# lab1_larionov_usb_rs232.net
KiCad netlist of a schematic drawn in Altium Designer
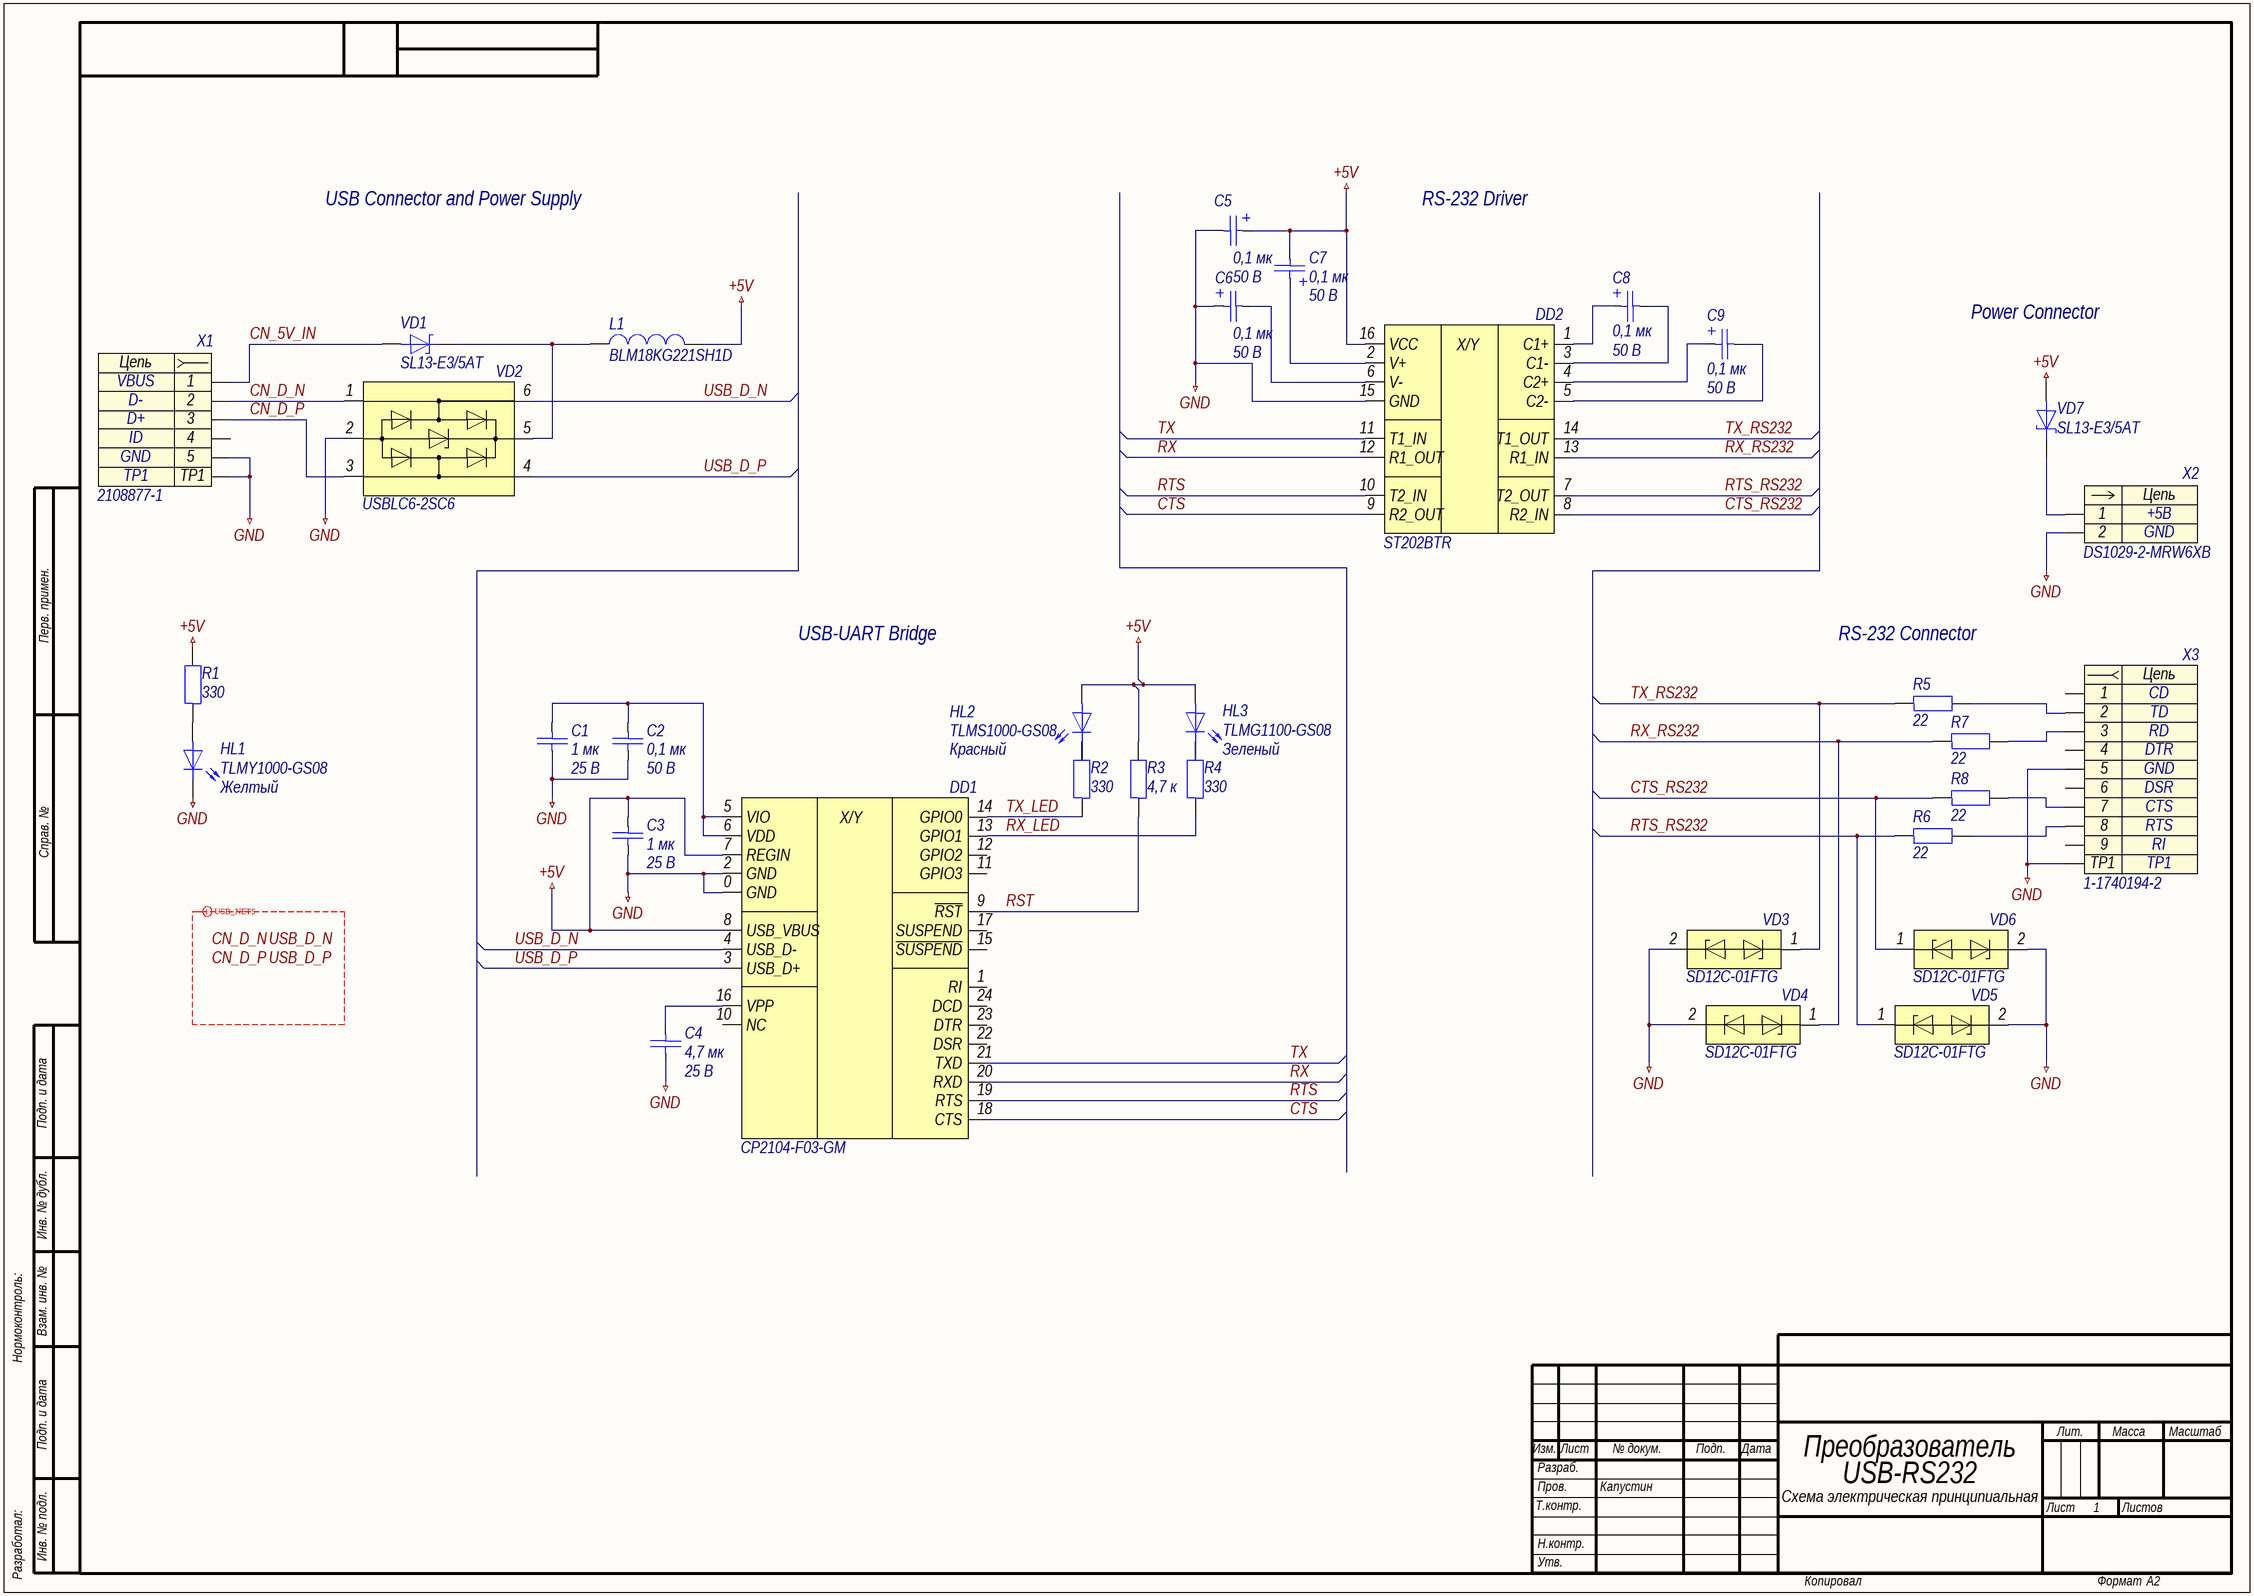
[diagram p0: lab1_larionov_usb_rs232.SchDoc]

(export (version "E")
  (design (tool "Eeschema 10.0.6"))
  (components
    (comp (ref "C1")
      (value "1 мк")
      (footprint "C0603")
      (description "=Описание")
      (fields (field (name "НАПРЯЖЕНИЕ") "25 В"))
      (libsource (lib "Database_Students") (part "CAPACITOR-NONPOLAR"))
    )
    (comp (ref "C2")
      (value "0,1 мк")
      (footprint "C0603")
      (description "=Описание")
      (fields (field (name "НАПРЯЖЕНИЕ") "50 В"))
      (libsource (lib "Database_Students") (part "CAPACITOR-NONPOLAR"))
    )
    (comp (ref "C3")
      (value "1 мк")
      (footprint "C0603")
      (description "=Описание")
      (fields (field (name "НАПРЯЖЕНИЕ") "25 В"))
      (libsource (lib "Database_Students") (part "CAPACITOR-NONPOLAR"))
    )
    (comp (ref "C4")
      (value "4,7 мк")
      (footprint "C0603")
      (description "=Описание")
      (fields (field (name "НАПРЯЖЕНИЕ") "25 В"))
      (libsource (lib "Database_Students") (part "CAPACITOR-NONPOLAR"))
    )
    (comp (ref "C5")
      (value "0,1 мк")
      (footprint "C1206POLAR")
      (description "=Описание")
      (fields (field (name "НАПРЯЖЕНИЕ") "50 В"))
      (libsource (lib "Database_Students") (part "CAPACITOR-POLAR"))
    )
    (comp (ref "C6")
      (value "0,1 мк")
      (footprint "C1206POLAR")
      (description "=Описание")
      (fields (field (name "НАПРЯЖЕНИЕ") "50 В"))
      (libsource (lib "Database_Students") (part "CAPACITOR-POLAR"))
    )
    (comp (ref "C7")
      (value "0,1 мк")
      (footprint "C1206POLAR")
      (description "=Описание")
      (fields (field (name "НАПРЯЖЕНИЕ") "50 В"))
      (libsource (lib "Database_Students") (part "CAPACITOR-POLAR"))
    )
    (comp (ref "C8")
      (value "0,1 мк")
      (footprint "C1206POLAR")
      (description "=Описание")
      (fields (field (name "НАПРЯЖЕНИЕ") "50 В"))
      (libsource (lib "Database_Students") (part "CAPACITOR-POLAR"))
    )
    (comp (ref "C9")
      (value "0,1 мк")
      (footprint "C1206POLAR")
      (description "=Описание")
      (fields (field (name "НАПРЯЖЕНИЕ") "50 В"))
      (libsource (lib "Database_Students") (part "CAPACITOR-POLAR"))
    )
    (comp (ref "DD1")
      (value "CP2104-F03-GM")
      (footprint "QFN-24-400X400X80")
      (description "=Описание")
      (libsource (lib "Database_Students") (part "CP2104-F03-GM"))
    )
    (comp (ref "DD2")
      (value "ST202BTR")
      (footprint "TSSOP-16")
      (description "=Описание")
      (libsource (lib "Database_Students") (part "ST202BTR"))
    )
    (comp (ref "HL1")
      (value "TLMY1000-GS08")
      (footprint "HL0603")
      (description "=Описание")
      (fields (field (name "COLOUR") "Желтый"))
      (libsource (lib "Database_Students") (part "LED-COMMON"))
    )
    (comp (ref "HL2")
      (value "TLMS1000-GS08")
      (footprint "HL0603")
      (description "=Описание")
      (fields (field (name "COLOUR") "Красный"))
      (libsource (lib "Database_Students") (part "LED-COMMON"))
    )
    (comp (ref "HL3")
      (value "TLMG1100-GS08")
      (footprint "HL0603")
      (description "=Описание")
      (fields (field (name "COLOUR") "Зеленый"))
      (libsource (lib "Database_Students") (part "LED-COMMON"))
    )
    (comp (ref "L1")
      (value "BLM18KG221SH1D")
      (footprint "BLM-2-0603")
      (description "=Описание")
      (libsource (lib "Database_Students") (part "FERRITE-BEAD"))
    )
    (comp (ref "R1")
      (value "330")
      (footprint "R0603")
      (description "=Описание")
      (libsource (lib "Database_Students") (part "R-COMMON"))
    )
    (comp (ref "R2")
      (value "330")
      (footprint "R0603")
      (description "=Описание")
      (libsource (lib "Database_Students") (part "R-COMMON"))
    )
    (comp (ref "R3")
      (value "4,7 к")
      (footprint "R0603")
      (description "=Описание")
      (libsource (lib "Database_Students") (part "R-COMMON"))
    )
    (comp (ref "R4")
      (value "330")
      (footprint "R0603")
      (description "=Описание")
      (libsource (lib "Database_Students") (part "R-COMMON"))
    )
    (comp (ref "R5")
      (value "22")
      (footprint "R0603")
      (description "=Описание")
      (libsource (lib "Database_Students") (part "R-COMMON"))
    )
    (comp (ref "R6")
      (value "22")
      (footprint "R0603")
      (description "=Описание")
      (libsource (lib "Database_Students") (part "R-COMMON"))
    )
    (comp (ref "R7")
      (value "22")
      (footprint "R0603")
      (description "=Описание")
      (libsource (lib "Database_Students") (part "R-COMMON"))
    )
    (comp (ref "R8")
      (value "22")
      (footprint "R0603")
      (description "=Описание")
      (libsource (lib "Database_Students") (part "R-COMMON"))
    )
    (comp (ref "VD1")
      (value "SL13-E3/5AT")
      (footprint "DO-214AC")
      (description "=Описание")
      (libsource (lib "Database_Students") (part "DIODE-SCHOTTKY"))
    )
    (comp (ref "VD2")
      (value "USBLC6-2SC6")
      (footprint "SOT-23-6")
      (description "=Описание")
      (libsource (lib "Database_Students") (part "USBLC6-2SC6"))
    )
    (comp (ref "VD3")
      (value "SD12C-01FTG")
      (footprint "SOD-323")
      (description "=Описание")
      (libsource (lib "") (part "ZENER-BI-DIRECTIONAL_1"))
    )
    (comp (ref "VD4")
      (value "SD12C-01FTG")
      (footprint "SOD-323")
      (description "=Описание")
      (libsource (lib "") (part "ZENER-BI-DIRECTIONAL_1"))
    )
    (comp (ref "VD5")
      (value "SD12C-01FTG")
      (footprint "SOD-323")
      (description "=Описание")
      (libsource (lib "Database_Students") (part "ZENER-BI-DIRECTIONAL"))
    )
    (comp (ref "VD6")
      (value "SD12C-01FTG")
      (footprint "SOD-323")
      (description "=Описание")
      (libsource (lib "Database_Students") (part "ZENER-BI-DIRECTIONAL"))
    )
    (comp (ref "VD7")
      (value "SL13-E3/5AT")
      (footprint "DO-214AC")
      (description "=Описание")
      (libsource (lib "Database_Students") (part "DIODE-SCHOTTKY"))
    )
    (comp (ref "X1")
      (value "2108877-1")
      (footprint "2108877-1")
      (libsource (lib "Database_Students") (part "HEADER-5-TP1-SCT"))
    )
    (comp (ref "X2")
      (value "DS1029-2-MRW6XB")
      (footprint "DS1029-2-MRW6XB")
      (description "=Описание")
      (libsource (lib "Database_Students") (part "HEADER-2-PLG"))
    )
    (comp (ref "X3")
      (value "1-1740194-2")
      (footprint "1-1740194-2")
      (libsource (lib "Database_Students") (part "HEADER-9-TP1-SCT"))
    )
  )
  (nets
    (net (code "1") (name "+5V") (class "Default")
      (node (ref "C3") (pin "2") (pinfunction "2_2") (pintype "passive"))
      (node (ref "C5") (pin "1") (pinfunction "1_1") (pintype "passive"))
      (node (ref "C7") (pin "2") (pinfunction "2_2") (pintype "passive"))
      (node (ref "DD1") (pin "7") (pinfunction "REGIN_7") (pintype "passive"))
      (node (ref "DD1") (pin "8") (pinfunction "USB_VBUS_8") (pintype "passive"))
      (node (ref "DD2") (pin "16") (pinfunction "VCC_16") (pintype "passive"))
      (node (ref "HL2") (pin "2") (pinfunction "2_2") (pintype "passive"))
      (node (ref "HL3") (pin "2") (pinfunction "2_2") (pintype "passive"))
      (node (ref "L1") (pin "2") (pinfunction "2_2") (pintype "passive"))
      (node (ref "R1") (pin "2") (pinfunction "2_2") (pintype "passive"))
      (node (ref "R3") (pin "2") (pinfunction "2_2") (pintype "passive"))
      (node (ref "VD7") (pin "2") (pinfunction "2_2") (pintype "passive"))
    )
    (net (code "2") (name "/CN_5V_IN") (class "Default")
      (node (ref "VD1") (pin "2") (pinfunction "2_2") (pintype "passive"))
      (node (ref "X1") (pin "1") (pinfunction "1_1") (pintype "passive"))
    )
    (net (code "3") (name "/CN_D_N") (class "Default")
      (node (ref "VD2") (pin "1") (pinfunction "1_1") (pintype "passive"))
      (node (ref "X1") (pin "2") (pinfunction "2_2") (pintype "passive"))
    )
    (net (code "4") (name "/CN_D_P") (class "Default")
      (node (ref "VD2") (pin "3") (pinfunction "3_3") (pintype "passive"))
      (node (ref "X1") (pin "3") (pinfunction "3_3") (pintype "passive"))
    )
    (net (code "5") (name "/CTS") (class "Default")
      (node (ref "DD1") (pin "18") (pinfunction "CTS_18") (pintype "passive"))
      (node (ref "DD2") (pin "9") (pinfunction "R2_OUT_9") (pintype "passive"))
    )
    (net (code "6") (name "/CTS_RS232") (class "Default")
      (node (ref "DD2") (pin "8") (pinfunction "R2_IN_8") (pintype "passive"))
      (node (ref "R8") (pin "1") (pinfunction "1_1") (pintype "passive"))
      (node (ref "VD6") (pin "1") (pinfunction "1_1") (pintype "passive"))
    )
    (net (code "7") (name "/RST") (class "Default")
      (node (ref "DD1") (pin "9") (pinfunction "~{RST}_9") (pintype "passive"))
      (node (ref "R3") (pin "1") (pinfunction "1_1") (pintype "passive"))
    )
    (net (code "8") (name "/RTS") (class "Default")
      (node (ref "DD1") (pin "19") (pinfunction "RTS_19") (pintype "passive"))
      (node (ref "DD2") (pin "10") (pinfunction "T2_IN_10") (pintype "passive"))
    )
    (net (code "9") (name "/RTS_RS232") (class "Default")
      (node (ref "DD2") (pin "7") (pinfunction "T2_OUT_7") (pintype "passive"))
      (node (ref "R6") (pin "1") (pinfunction "1_1") (pintype "passive"))
      (node (ref "VD5") (pin "1") (pinfunction "1_1") (pintype "passive"))
    )
    (net (code "10") (name "/RX") (class "Default")
      (node (ref "DD1") (pin "20") (pinfunction "RXD_20") (pintype "passive"))
      (node (ref "DD2") (pin "12") (pinfunction "R1_OUT_12") (pintype "passive"))
    )
    (net (code "11") (name "/RX_LED") (class "Default")
      (node (ref "DD1") (pin "13") (pinfunction "GPIO1_13") (pintype "passive"))
      (node (ref "R4") (pin "1") (pinfunction "1_1") (pintype "passive"))
    )
    (net (code "12") (name "/RX_RS232") (class "Default")
      (node (ref "DD2") (pin "13") (pinfunction "R1_IN_13") (pintype "passive"))
      (node (ref "R7") (pin "1") (pinfunction "1_1") (pintype "passive"))
      (node (ref "VD4") (pin "1") (pinfunction "1_1") (pintype "passive"))
    )
    (net (code "13") (name "/TX") (class "Default")
      (node (ref "DD1") (pin "21") (pinfunction "TXD_21") (pintype "passive"))
      (node (ref "DD2") (pin "11") (pinfunction "T1_IN_11") (pintype "passive"))
    )
    (net (code "14") (name "/TX_LED") (class "Default")
      (node (ref "DD1") (pin "14") (pinfunction "GPIO0_14") (pintype "passive"))
      (node (ref "R2") (pin "1") (pinfunction "1_1") (pintype "passive"))
    )
    (net (code "15") (name "/TX_RS232") (class "Default")
      (node (ref "DD2") (pin "14") (pinfunction "T1_OUT_14") (pintype "passive"))
      (node (ref "R5") (pin "1") (pinfunction "1_1") (pintype "passive"))
      (node (ref "VD3") (pin "1") (pinfunction "1_1") (pintype "passive"))
    )
    (net (code "16") (name "/USB_D_N") (class "Default")
      (node (ref "DD1") (pin "4") (pinfunction "USB_D-_4") (pintype "passive"))
      (node (ref "VD2") (pin "6") (pinfunction "6_6") (pintype "passive"))
    )
    (net (code "17") (name "/USB_D_P") (class "Default")
      (node (ref "DD1") (pin "3") (pinfunction "USB_D+_3") (pintype "passive"))
      (node (ref "VD2") (pin "4") (pinfunction "4_4") (pintype "passive"))
    )
    (net (code "18") (name "GND") (class "Default")
      (node (ref "C1") (pin "1") (pinfunction "1_1") (pintype "passive"))
      (node (ref "C2") (pin "1") (pinfunction "1_1") (pintype "passive"))
      (node (ref "C3") (pin "1") (pinfunction "1_1") (pintype "passive"))
      (node (ref "C4") (pin "1") (pinfunction "1_1") (pintype "passive"))
      (node (ref "C5") (pin "2") (pinfunction "2_2") (pintype "passive"))
      (node (ref "C6") (pin "1") (pinfunction "1_1") (pintype "passive"))
      (node (ref "DD1") (pin "0") (pinfunction "GND_0") (pintype "passive"))
      (node (ref "DD1") (pin "2") (pinfunction "GND_2") (pintype "passive"))
      (node (ref "DD2") (pin "15") (pinfunction "GND_15") (pintype "passive"))
      (node (ref "HL1") (pin "1") (pinfunction "1_1") (pintype "passive"))
      (node (ref "VD2") (pin "2") (pinfunction "2_2") (pintype "passive"))
      (node (ref "VD3") (pin "2") (pinfunction "2_2") (pintype "passive"))
      (node (ref "VD4") (pin "2") (pinfunction "2_2") (pintype "passive"))
      (node (ref "VD5") (pin "2") (pinfunction "2_2") (pintype "passive"))
      (node (ref "VD6") (pin "2") (pinfunction "2_2") (pintype "passive"))
      (node (ref "X1") (pin "5") (pinfunction "5_5") (pintype "passive"))
      (node (ref "X1") (pin "TP1") (pinfunction "TP1_TP1") (pintype "passive"))
      (node (ref "X2") (pin "2") (pinfunction "2_2") (pintype "passive"))
      (node (ref "X3") (pin "5") (pinfunction "5_5") (pintype "passive"))
      (node (ref "X3") (pin "TP1") (pinfunction "TP1_TP1") (pintype "passive"))
    )
    (net (code "19") (name "Net-(DD1-VDD)") (class "Default")
      (node (ref "C1") (pin "2") (pinfunction "2_2") (pintype "passive"))
      (node (ref "C2") (pin "2") (pinfunction "2_2") (pintype "passive"))
      (node (ref "DD1") (pin "5") (pinfunction "VIO_5") (pintype "passive"))
      (node (ref "DD1") (pin "6") (pinfunction "VDD_6") (pintype "passive"))
    )
    (net (code "20") (name "Net-(DD1-VPP)") (class "Default")
      (node (ref "C4") (pin "2") (pinfunction "2_2") (pintype "passive"))
      (node (ref "DD1") (pin "16") (pinfunction "VPP_16") (pintype "passive"))
    )
    (net (code "21") (name "Net-(DD2-C1+)") (class "Default")
      (node (ref "C8") (pin "1") (pinfunction "1_1") (pintype "passive"))
      (node (ref "DD2") (pin "1") (pinfunction "C1+_1") (pintype "passive"))
    )
    (net (code "22") (name "Net-(DD2-C1-)") (class "Default")
      (node (ref "C8") (pin "2") (pinfunction "2_2") (pintype "passive"))
      (node (ref "DD2") (pin "3") (pinfunction "C1-_3") (pintype "passive"))
    )
    (net (code "23") (name "Net-(DD2-C2+)") (class "Default")
      (node (ref "C9") (pin "1") (pinfunction "1_1") (pintype "passive"))
      (node (ref "DD2") (pin "4") (pinfunction "C2+_4") (pintype "passive"))
    )
    (net (code "24") (name "Net-(DD2-C2-)") (class "Default")
      (node (ref "C9") (pin "2") (pinfunction "2_2") (pintype "passive"))
      (node (ref "DD2") (pin "5") (pinfunction "C2-_5") (pintype "passive"))
    )
    (net (code "25") (name "Net-(DD2-V+)") (class "Default")
      (node (ref "C7") (pin "1") (pinfunction "1_1") (pintype "passive"))
      (node (ref "DD2") (pin "2") (pinfunction "V+_2") (pintype "passive"))
    )
    (net (code "26") (name "Net-(DD2-V-)") (class "Default")
      (node (ref "C6") (pin "2") (pinfunction "2_2") (pintype "passive"))
      (node (ref "DD2") (pin "6") (pinfunction "V-_6") (pintype "passive"))
    )
    (net (code "27") (name "Net-(HL1-Pad2)") (class "Default")
      (node (ref "HL1") (pin "2") (pinfunction "2_2") (pintype "passive"))
      (node (ref "R1") (pin "1") (pinfunction "1_1") (pintype "passive"))
    )
    (net (code "28") (name "Net-(HL2-Pad1)") (class "Default")
      (node (ref "HL2") (pin "1") (pinfunction "1_1") (pintype "passive"))
      (node (ref "R2") (pin "2") (pinfunction "2_2") (pintype "passive"))
    )
    (net (code "29") (name "Net-(HL3-Pad1)") (class "Default")
      (node (ref "HL3") (pin "1") (pinfunction "1_1") (pintype "passive"))
      (node (ref "R4") (pin "2") (pinfunction "2_2") (pintype "passive"))
    )
    (net (code "30") (name "Net-(L1-Pad1)") (class "Default")
      (node (ref "L1") (pin "1") (pinfunction "1_1") (pintype "passive"))
      (node (ref "VD1") (pin "1") (pinfunction "1_1") (pintype "passive"))
      (node (ref "VD2") (pin "5") (pinfunction "5_5") (pintype "passive"))
    )
    (net (code "31") (name "Net-(R5-Pad2)") (class "Default")
      (node (ref "R5") (pin "2") (pinfunction "2_2") (pintype "passive"))
      (node (ref "X3") (pin "2") (pinfunction "2_2") (pintype "passive"))
    )
    (net (code "32") (name "Net-(R6-Pad2)") (class "Default")
      (node (ref "R6") (pin "2") (pinfunction "2_2") (pintype "passive"))
      (node (ref "X3") (pin "8") (pinfunction "8_8") (pintype "passive"))
    )
    (net (code "33") (name "Net-(R7-Pad2)") (class "Default")
      (node (ref "R7") (pin "2") (pinfunction "2_2") (pintype "passive"))
      (node (ref "X3") (pin "3") (pinfunction "3_3") (pintype "passive"))
    )
    (net (code "34") (name "Net-(R8-Pad2)") (class "Default")
      (node (ref "R8") (pin "2") (pinfunction "2_2") (pintype "passive"))
      (node (ref "X3") (pin "7") (pinfunction "7_7") (pintype "passive"))
    )
    (net (code "35") (name "Net-(VD7-Pad1)") (class "Default")
      (node (ref "VD7") (pin "1") (pinfunction "1_1") (pintype "passive"))
      (node (ref "X2") (pin "1") (pinfunction "1_1") (pintype "passive"))
    )
    (net (code "36") (name "unconnected-(DD1-DCD-Pad24)") (class "Default")
      (node (ref "DD1") (pin "24") (pinfunction "DCD_24") (pintype "passive"))
    )
    (net (code "37") (name "unconnected-(DD1-DSR-Pad22)") (class "Default")
      (node (ref "DD1") (pin "22") (pinfunction "DSR_22") (pintype "passive"))
    )
    (net (code "38") (name "unconnected-(DD1-DTR-Pad23)") (class "Default")
      (node (ref "DD1") (pin "23") (pinfunction "DTR_23") (pintype "passive"))
    )
    (net (code "39") (name "unconnected-(DD1-GPIO2-Pad12)") (class "Default")
      (node (ref "DD1") (pin "12") (pinfunction "GPIO2_12") (pintype "passive"))
    )
    (net (code "40") (name "unconnected-(DD1-GPIO3-Pad11)") (class "Default")
      (node (ref "DD1") (pin "11") (pinfunction "GPIO3_11") (pintype "passive"))
    )
    (net (code "41") (name "unconnected-(DD1-NC-Pad10)") (class "Default")
      (node (ref "DD1") (pin "10") (pinfunction "NC_10") (pintype "passive"))
    )
    (net (code "42") (name "unconnected-(DD1-RI-Pad1)") (class "Default")
      (node (ref "DD1") (pin "1") (pinfunction "RI_1") (pintype "passive"))
    )
    (net (code "43") (name "unconnected-(DD1-SUSPEND-Pad17)") (class "Default")
      (node (ref "DD1") (pin "17") (pinfunction "SUSPEND_17") (pintype "passive"))
    )
    (net (code "44") (name "unconnected-(DD1-~{SUSPEND}-Pad15)") (class "Default")
      (node (ref "DD1") (pin "15") (pinfunction "~{SUSPEND}_15") (pintype "passive"))
    )
    (net (code "45") (name "unconnected-(X1-Pad4)") (class "Default")
      (node (ref "X1") (pin "4") (pinfunction "4_4") (pintype "passive"))
    )
    (net (code "46") (name "unconnected-(X3-Pad1)") (class "Default")
      (node (ref "X3") (pin "1") (pinfunction "1_1") (pintype "passive"))
    )
    (net (code "47") (name "unconnected-(X3-Pad4)") (class "Default")
      (node (ref "X3") (pin "4") (pinfunction "4_4") (pintype "passive"))
    )
    (net (code "48") (name "unconnected-(X3-Pad6)") (class "Default")
      (node (ref "X3") (pin "6") (pinfunction "6_6") (pintype "passive"))
    )
    (net (code "49") (name "unconnected-(X3-Pad9)") (class "Default")
      (node (ref "X3") (pin "9") (pinfunction "9_9") (pintype "passive"))
    )
  )
)
